# Flash_Memory.net
KiCad netlist of a schematic drawn in Altium Designer
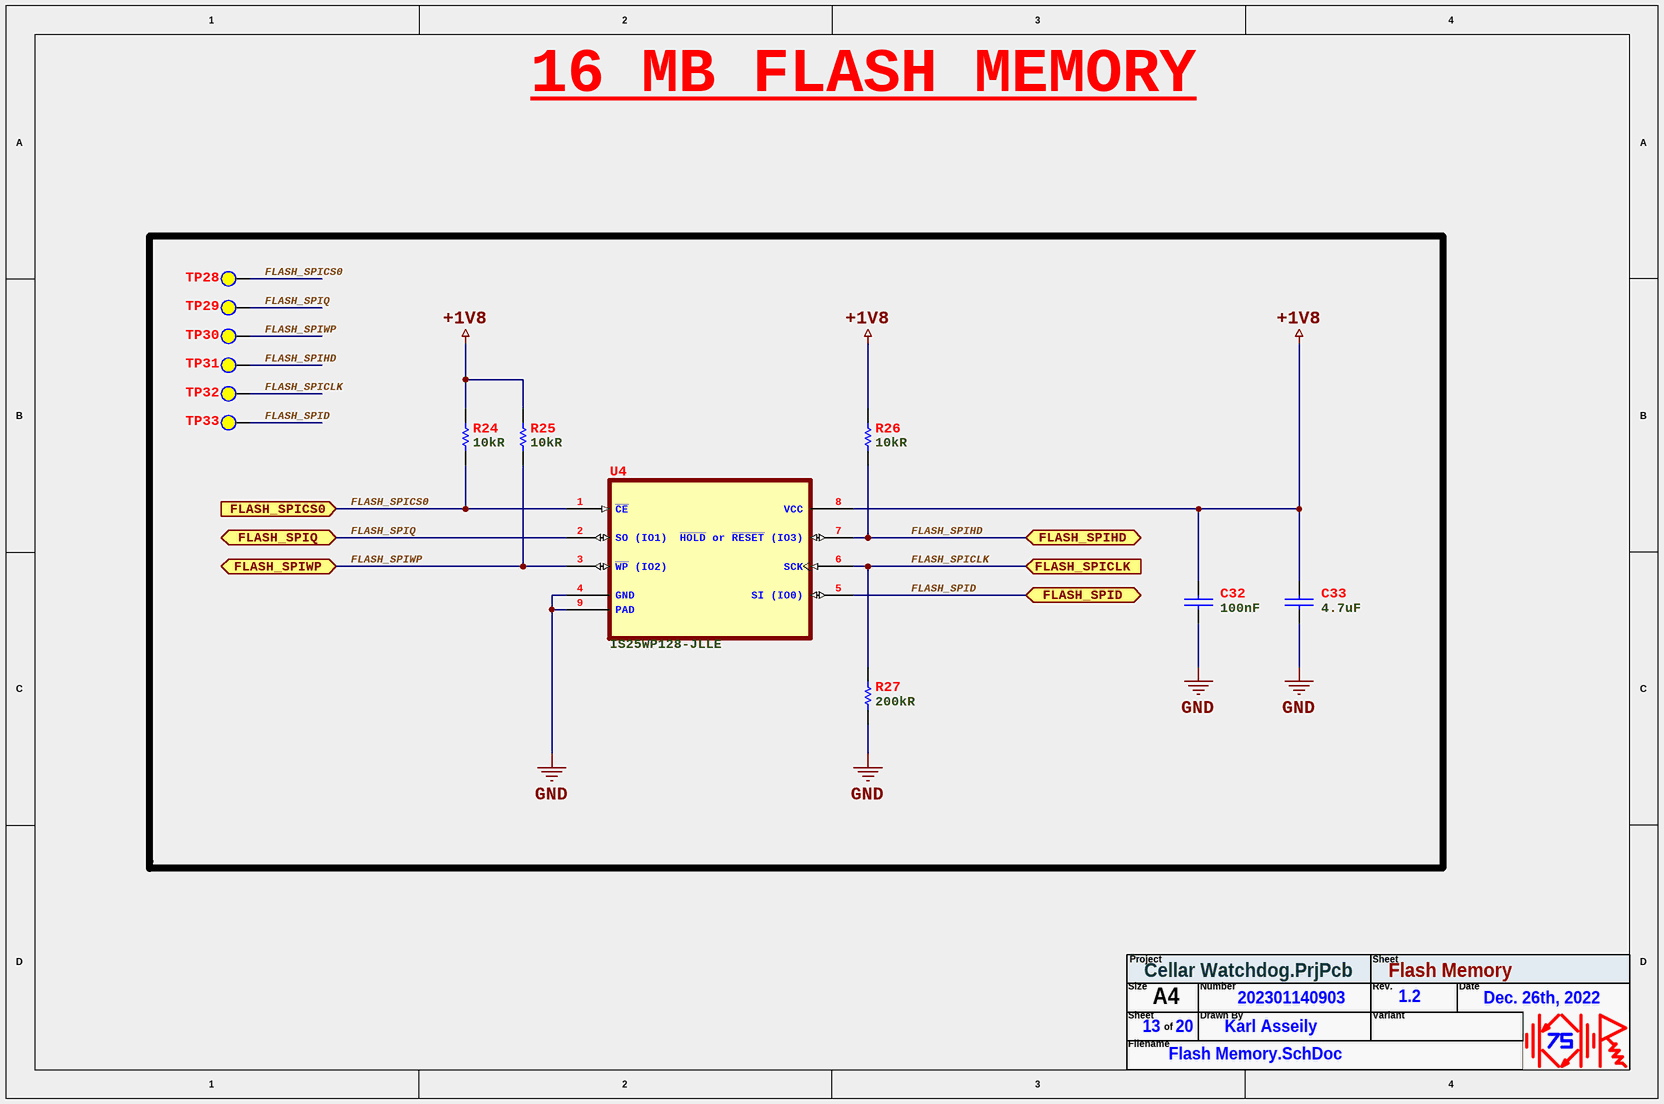
[diagram p0: Flash Memory.SchDoc]

(export (version "E")
  (design (tool "Eeschema 10.0.6"))
  (components
    (comp (ref "C32")
      (value "100nF")
      (footprint "CAP_0603")
      (description "0.1 µF ±10% 50V Ceramic Capacitor X7R 0603 (1608 Metric)")
      (fields
        (field (name "MANUFACTURER") "Yageo")
        (field (name "MANUFACTURER PART NUMBER") "CC0603KRX7R9BB104")
      )
      (libsource (lib "Cellar Watchdog") (part "CAP_0.1uF-50V-10%_0603"))
    )
    (comp (ref "C33")
      (value "4.7uF")
      (footprint "CAP_0805")
      (description "4.7 µF ±10% 25V Ceramic Capacitor X7R 0805 (2012 Metric)")
      (fields
        (field (name "MANUFACTURER") "Yageo")
        (field (name "MANUFACTURER PART NUMBER") "CC0805KKX7R8BB475")
      )
      (libsource (lib "Cellar Watchdog") (part "CAP_4.7uF-25V-10%_0805"))
    )
    (comp (ref "R24")
      (value "10kR")
      (footprint "RES_0603")
      (description "10 kOhms ±1% 0.1W, 1/10W Chip Resistor 0603 (1608 Metric) Moisture Resistant Thick Film")
      (fields
        (field (name "MANUFACTURER") "Yageo")
        (field (name "MANUFACTURER PART NUMBER") "RC0603FR-0710KL")
      )
      (libsource (lib "Cellar Watchdog") (part "RES_10kR-100mW-1%_0603"))
    )
    (comp (ref "R25")
      (value "10kR")
      (footprint "RES_0603")
      (description "10 kOhms ±1% 0.1W, 1/10W Chip Resistor 0603 (1608 Metric) Moisture Resistant Thick Film")
      (fields
        (field (name "MANUFACTURER") "Yageo")
        (field (name "MANUFACTURER PART NUMBER") "RC0603FR-0710KL")
      )
      (libsource (lib "Cellar Watchdog") (part "RES_10kR-100mW-1%_0603"))
    )
    (comp (ref "R26")
      (value "10kR")
      (footprint "RES_0603")
      (description "10 kOhms ±1% 0.1W, 1/10W Chip Resistor 0603 (1608 Metric) Moisture Resistant Thick Film")
      (fields
        (field (name "MANUFACTURER") "Yageo")
        (field (name "MANUFACTURER PART NUMBER") "RC0603FR-0710KL")
      )
      (libsource (lib "Cellar Watchdog") (part "RES_10kR-100mW-1%_0603"))
    )
    (comp (ref "R27")
      (value "200kR")
      (footprint "RES_0603")
      (description "200 kOhms ±1% 0.1W, 1/10W Chip Resistor 0603 (1608 Metric) Moisture Resistant Thick Film")
      (fields
        (field (name "MANUFACTURER") "Yageo")
        (field (name "MANUFACTURER PART NUMBER") "RC0603FR-07200KL")
      )
      (libsource (lib "Cellar Watchdog") (part "RES_200kR-100mW-1%_0603"))
    )
    (comp (ref "TP28")
      (value "SPICS0")
      (footprint "TEST POINT PAD")
      (description "PCB Test Point")
      (libsource (lib "Cellar Watchdog") (part "Test Point"))
    )
    (comp (ref "TP29")
      (value "SPIQ")
      (footprint "TEST POINT PAD")
      (description "PCB Test Point")
      (libsource (lib "Cellar Watchdog") (part "Test Point"))
    )
    (comp (ref "TP30")
      (value "SPIWP")
      (footprint "TEST POINT PAD")
      (description "PCB Test Point")
      (libsource (lib "Cellar Watchdog") (part "Test Point"))
    )
    (comp (ref "TP31")
      (value "SPIHD")
      (footprint "TEST POINT PAD")
      (description "PCB Test Point")
      (libsource (lib "Cellar Watchdog") (part "Test Point"))
    )
    (comp (ref "TP32")
      (value "SPICLK")
      (footprint "TEST POINT PAD")
      (description "PCB Test Point")
      (libsource (lib "Cellar Watchdog") (part "Test Point"))
    )
    (comp (ref "TP33")
      (value "SPID")
      (footprint "TEST POINT PAD")
      (description "PCB Test Point")
      (libsource (lib "Cellar Watchdog") (part "Test Point"))
    )
    (comp (ref "U4")
      (value "IS25WP128-JLLE")
      (footprint "IC_SON127P800X600X80-9N")
      (description "NOR Flash Serial (SPI, Dual SPI, Quad SPI) 1.8V 128M-bit 16M x 8 8ns 8-Pin WSON EP")
      (fields (field (name "MANUFACTURER") "ISSI"))
      (libsource (lib "Cellar Watchdog") (part "IC_IS25WP128-JLLE"))
    )
  )
  (nets
    (net (code "1") (name "+1V8") (class "Default")
      (node (ref "C32") (pin "1") (pinfunction "1_1") (pintype "passive"))
      (node (ref "C33") (pin "1") (pinfunction "1_1") (pintype "passive"))
      (node (ref "R24") (pin "2") (pinfunction "2_2") (pintype "passive"))
      (node (ref "R25") (pin "2") (pinfunction "2_2") (pintype "passive"))
      (node (ref "R26") (pin "2") (pinfunction "2_2") (pintype "passive"))
      (node (ref "U4") (pin "8") (pinfunction "VCC_8") (pintype "power_in"))
    )
    (net (code "2") (name "/FLASH_SPICLK") (class "Default")
      (node (ref "R27") (pin "1") (pinfunction "1_1") (pintype "passive"))
      (node (ref "TP32") (pin "TP") (pinfunction "TP_TP") (pintype "passive"))
      (node (ref "U4") (pin "6") (pinfunction "SCK_6") (pintype "input"))
    )
    (net (code "3") (name "/FLASH_SPICS0") (class "Default")
      (node (ref "R24") (pin "1") (pinfunction "1_1") (pintype "passive"))
      (node (ref "TP28") (pin "TP") (pinfunction "TP_TP") (pintype "passive"))
      (node (ref "U4") (pin "1") (pinfunction "CE_1") (pintype "input"))
    )
    (net (code "4") (name "/FLASH_SPID") (class "Default")
      (node (ref "TP33") (pin "TP") (pinfunction "TP_TP") (pintype "passive"))
      (node (ref "U4") (pin "5") (pinfunction "SI_(IO0)_5") (pintype "bidirectional"))
    )
    (net (code "5") (name "/FLASH_SPIHD") (class "Default")
      (node (ref "R26") (pin "1") (pinfunction "1_1") (pintype "passive"))
      (node (ref "TP31") (pin "TP") (pinfunction "TP_TP") (pintype "passive"))
      (node (ref "U4") (pin "7") (pinfunction "~{HOLD}_or_~{RESET}_(IO3)_7") (pintype "bidirectional"))
    )
    (net (code "6") (name "/FLASH_SPIQ") (class "Default")
      (node (ref "TP29") (pin "TP") (pinfunction "TP_TP") (pintype "passive"))
      (node (ref "U4") (pin "2") (pinfunction "SO_(IO1)_2") (pintype "bidirectional"))
    )
    (net (code "7") (name "/FLASH_SPIWP") (class "Default")
      (node (ref "R25") (pin "1") (pinfunction "1_1") (pintype "passive"))
      (node (ref "TP30") (pin "TP") (pinfunction "TP_TP") (pintype "passive"))
      (node (ref "U4") (pin "3") (pinfunction "~{WP}_(IO2)_3") (pintype "bidirectional"))
    )
    (net (code "8") (name "GND") (class "Default")
      (node (ref "C32") (pin "2") (pinfunction "2_2") (pintype "passive"))
      (node (ref "C33") (pin "2") (pinfunction "2_2") (pintype "passive"))
      (node (ref "R27") (pin "2") (pinfunction "2_2") (pintype "passive"))
      (node (ref "U4") (pin "4") (pinfunction "GND_4") (pintype "power_in"))
      (node (ref "U4") (pin "9") (pinfunction "PAD_9") (pintype "power_in"))
    )
  )
)
